# Base_SMD.net
KiCad netlist of a schematic drawn in EAGLE
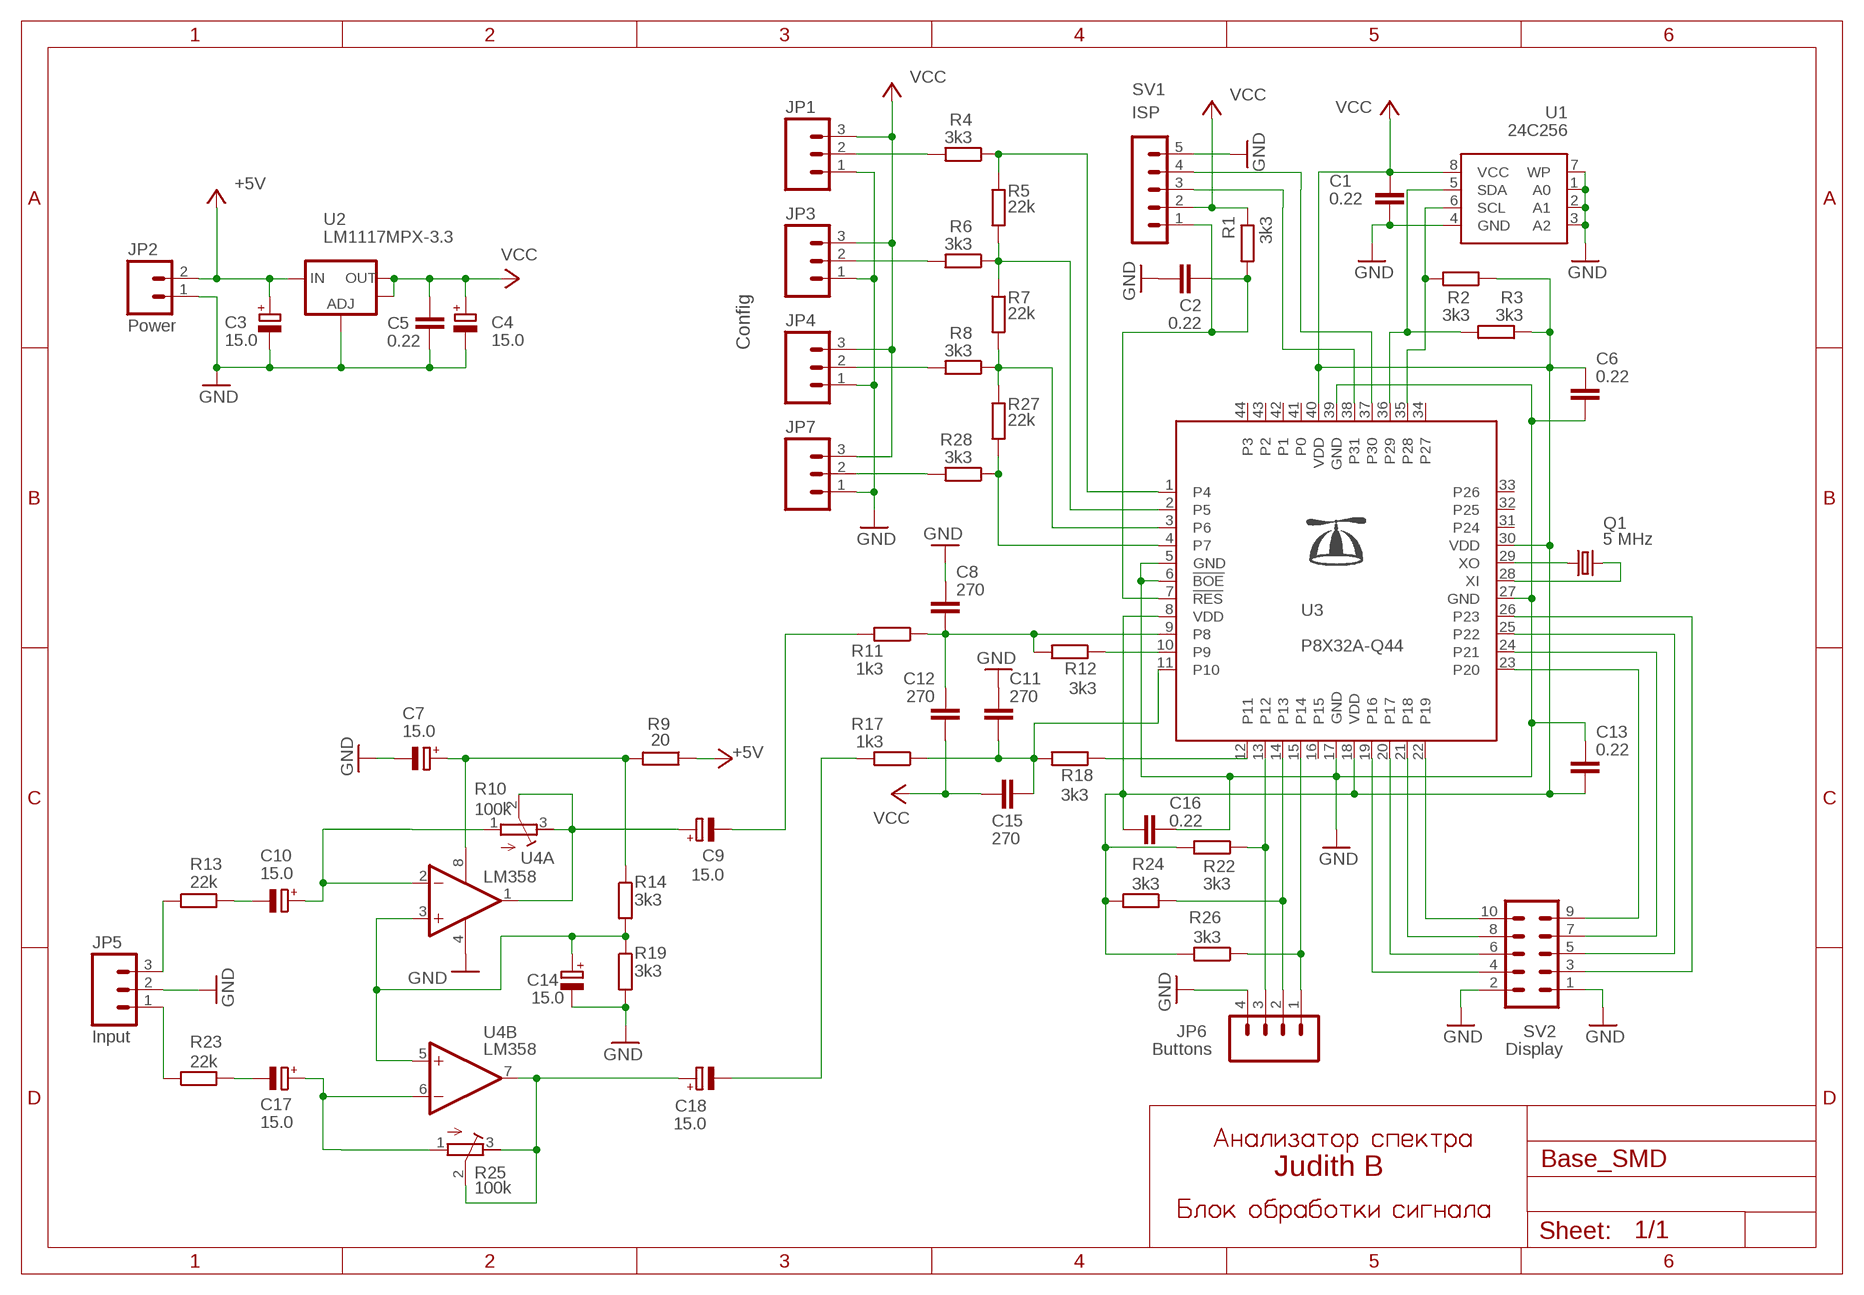
[diagram p0: schematic, sheet 1]

(export (version "E")
  (design (tool "Eeschema 10.0.6"))
  (components
    (comp (ref "C1")
      (value "0.22")
      (footprint "eagle-import:C0805")
      (libsource (lib "eagle-import") (part "C-EUC0805"))
    )
    (comp (ref "C2")
      (value "0.22")
      (footprint "eagle-import:C0805")
      (libsource (lib "eagle-import") (part "C-EUC0805"))
    )
    (comp (ref "C3")
      (value "15.0")
      (footprint "eagle-import:SMC_B")
      (libsource (lib "eagle-import") (part "CPOL-EUSMCB"))
    )
    (comp (ref "C4")
      (value "15.0")
      (footprint "eagle-import:SMC_B")
      (libsource (lib "eagle-import") (part "CPOL-EUSMCB"))
    )
    (comp (ref "C5")
      (value "0.22")
      (footprint "eagle-import:C0805")
      (libsource (lib "eagle-import") (part "C-EUC0805"))
    )
    (comp (ref "C6")
      (value "0.22")
      (footprint "eagle-import:C0805")
      (libsource (lib "eagle-import") (part "C-EUC0805"))
    )
    (comp (ref "C7")
      (value "15.0")
      (footprint "eagle-import:SMC_B")
      (libsource (lib "eagle-import") (part "CPOL-EUSMCB"))
    )
    (comp (ref "C8")
      (value "270")
      (footprint "eagle-import:C0805")
      (libsource (lib "eagle-import") (part "C-EUC0805"))
    )
    (comp (ref "C9")
      (value "15.0")
      (footprint "eagle-import:SMC_B")
      (libsource (lib "eagle-import") (part "CPOL-EUSMCB"))
    )
    (comp (ref "C10")
      (value "15.0")
      (footprint "eagle-import:SMC_B")
      (libsource (lib "eagle-import") (part "CPOL-EUSMCB"))
    )
    (comp (ref "C11")
      (value "270")
      (footprint "eagle-import:C0805")
      (libsource (lib "eagle-import") (part "C-EUC0805"))
    )
    (comp (ref "C12")
      (value "270")
      (footprint "eagle-import:C0805")
      (libsource (lib "eagle-import") (part "C-EUC0805"))
    )
    (comp (ref "C13")
      (value "0.22")
      (footprint "eagle-import:C0805")
      (libsource (lib "eagle-import") (part "C-EUC0805"))
    )
    (comp (ref "C14")
      (value "15.0")
      (footprint "eagle-import:SMC_B")
      (libsource (lib "eagle-import") (part "CPOL-EUSMCB"))
    )
    (comp (ref "C15")
      (value "270")
      (footprint "eagle-import:C0805")
      (libsource (lib "eagle-import") (part "C-EUC0805"))
    )
    (comp (ref "C16")
      (value "0.22")
      (footprint "eagle-import:C0805")
      (libsource (lib "eagle-import") (part "C-EUC0805"))
    )
    (comp (ref "C17")
      (value "15.0")
      (footprint "eagle-import:SMC_B")
      (libsource (lib "eagle-import") (part "CPOL-EUSMCB"))
    )
    (comp (ref "C18")
      (value "15.0")
      (footprint "eagle-import:SMC_B")
      (libsource (lib "eagle-import") (part "CPOL-EUSMCB"))
    )
    (comp (ref "JP1")
      (value "M03PTH")
      (footprint "eagle-import:1X03")
      (libsource (lib "eagle-import") (part "M03PTH"))
    )
    (comp (ref "JP2")
      (value "Power")
      (footprint "eagle-import:1X02")
      (libsource (lib "eagle-import") (part "M02PTH"))
    )
    (comp (ref "JP3")
      (value "M03PTH")
      (footprint "eagle-import:1X03")
      (libsource (lib "eagle-import") (part "M03PTH"))
    )
    (comp (ref "JP4")
      (value "M03PTH")
      (footprint "eagle-import:1X03")
      (libsource (lib "eagle-import") (part "M03PTH"))
    )
    (comp (ref "JP5")
      (value "Input")
      (footprint "eagle-import:1X03")
      (libsource (lib "eagle-import") (part "M03PTH"))
    )
    (comp (ref "JP6")
      (value "Buttons")
      (footprint "eagle-import:1X04")
      (libsource (lib "eagle-import") (part "M04PTH"))
    )
    (comp (ref "JP7")
      (value "M03PTH")
      (footprint "eagle-import:1X03")
      (libsource (lib "eagle-import") (part "M03PTH"))
    )
    (comp (ref "Q1")
      (value "5 MHz")
      (footprint "eagle-import:HC49_S")
      (libsource (lib "eagle-import") (part "CRYSTALHC49S"))
    )
    (comp (ref "R1")
      (value "3k3")
      (footprint "eagle-import:R0805")
      (libsource (lib "eagle-import") (part "R-0805"))
    )
    (comp (ref "R2")
      (value "3k3")
      (footprint "eagle-import:R0805")
      (libsource (lib "eagle-import") (part "R-0805"))
    )
    (comp (ref "R3")
      (value "3k3")
      (footprint "eagle-import:R0805")
      (libsource (lib "eagle-import") (part "R-0805"))
    )
    (comp (ref "R4")
      (value "3k3")
      (footprint "eagle-import:R0805")
      (libsource (lib "eagle-import") (part "R-0805"))
    )
    (comp (ref "R5")
      (value "22k")
      (footprint "eagle-import:R0805")
      (libsource (lib "eagle-import") (part "R-0805"))
    )
    (comp (ref "R6")
      (value "3k3")
      (footprint "eagle-import:R0805")
      (libsource (lib "eagle-import") (part "R-0805"))
    )
    (comp (ref "R7")
      (value "22k")
      (footprint "eagle-import:R0805")
      (libsource (lib "eagle-import") (part "R-0805"))
    )
    (comp (ref "R8")
      (value "3k3")
      (footprint "eagle-import:R0805")
      (libsource (lib "eagle-import") (part "R-0805"))
    )
    (comp (ref "R9")
      (value "20")
      (footprint "eagle-import:R0805")
      (libsource (lib "eagle-import") (part "R-0805"))
    )
    (comp (ref "R10")
      (value "100k")
      (footprint "eagle-import:RTRIM3296W")
      (libsource (lib "eagle-import") (part "R-TRIMM3296W"))
    )
    (comp (ref "R11")
      (value "1k3")
      (footprint "eagle-import:R0805")
      (libsource (lib "eagle-import") (part "R-0805"))
    )
    (comp (ref "R12")
      (value "3k3")
      (footprint "eagle-import:R0805")
      (libsource (lib "eagle-import") (part "R-0805"))
    )
    (comp (ref "R13")
      (value "22k")
      (footprint "eagle-import:R0805")
      (libsource (lib "eagle-import") (part "R-0805"))
    )
    (comp (ref "R14")
      (value "3k3")
      (footprint "eagle-import:R0805")
      (libsource (lib "eagle-import") (part "R-0805"))
    )
    (comp (ref "R17")
      (value "1k3")
      (footprint "eagle-import:R0805")
      (libsource (lib "eagle-import") (part "R-0805"))
    )
    (comp (ref "R18")
      (value "3k3")
      (footprint "eagle-import:R0805")
      (libsource (lib "eagle-import") (part "R-0805"))
    )
    (comp (ref "R19")
      (value "3k3")
      (footprint "eagle-import:R0805")
      (libsource (lib "eagle-import") (part "R-0805"))
    )
    (comp (ref "R22")
      (value "3k3")
      (footprint "eagle-import:R0805")
      (libsource (lib "eagle-import") (part "R-0805"))
    )
    (comp (ref "R23")
      (value "22k")
      (footprint "eagle-import:R0805")
      (libsource (lib "eagle-import") (part "R-0805"))
    )
    (comp (ref "R24")
      (value "3k3")
      (footprint "eagle-import:R0805")
      (libsource (lib "eagle-import") (part "R-0805"))
    )
    (comp (ref "R25")
      (value "100k")
      (footprint "eagle-import:RTRIM3296W")
      (libsource (lib "eagle-import") (part "R-TRIMM3296W"))
    )
    (comp (ref "R26")
      (value "3k3")
      (footprint "eagle-import:R0805")
      (libsource (lib "eagle-import") (part "R-0805"))
    )
    (comp (ref "R27")
      (value "22k")
      (footprint "eagle-import:R0805")
      (libsource (lib "eagle-import") (part "R-0805"))
    )
    (comp (ref "R28")
      (value "3k3")
      (footprint "eagle-import:R0805")
      (libsource (lib "eagle-import") (part "R-0805"))
    )
    (comp (ref "SV1")
      (value "ISP")
      (footprint "eagle-import:MA05-1")
      (libsource (lib "eagle-import") (part "MA05-1"))
    )
    (comp (ref "SV2")
      (value "Display")
      (footprint "eagle-import:MA05-2")
      (libsource (lib "eagle-import") (part "MA05-2"))
    )
    (comp (ref "U1")
      (value "24C256")
      (footprint "eagle-import:SO08")
      (libsource (lib "eagle-import") (part "I2C_EEPROM"))
    )
    (comp (ref "U2")
      (value "LM1117MPX-3.3")
      (footprint "eagle-import:SOT223")
      (libsource (lib "eagle-import") (part "V_REG_LM1117SOT223"))
    )
    (comp (ref "U3")
      (value "P8X32A-Q44")
      (footprint "eagle-import:SQFP-S-10X10-44")
      (libsource (lib "eagle-import") (part "P8X32A-Q44"))
    )
    (comp (ref "U4")
      (value "LM358")
      (footprint "eagle-import:SO08")
      (libsource (lib "eagle-import") (part "TL072D"))
    )
  )
  (nets
    (net (code "1") (name "+5V") (class "Default")
      (node (ref "C3") (pin "+") (pinfunction "+_+") (pintype "passive"))
      (node (ref "JP2") (pin "2") (pinfunction "2_2") (pintype "passive"))
      (node (ref "R9") (pin "1") (pinfunction "1_1") (pintype "passive"))
      (node (ref "U2") (pin "3") (pinfunction "IN_3") (pintype "input"))
    )
    (net (code "2") (name "GND") (class "Default")
      (node (ref "C1") (pin "2") (pinfunction "2_2") (pintype "passive"))
      (node (ref "C11") (pin "1") (pinfunction "1_1") (pintype "passive"))
      (node (ref "C13") (pin "1") (pinfunction "1_1") (pintype "passive"))
      (node (ref "C14") (pin "-") (pinfunction "-_-") (pintype "passive"))
      (node (ref "C16") (pin "2") (pinfunction "2_2") (pintype "passive"))
      (node (ref "C2") (pin "1") (pinfunction "1_1") (pintype "passive"))
      (node (ref "C3") (pin "-") (pinfunction "-_-") (pintype "passive"))
      (node (ref "C4") (pin "-") (pinfunction "-_-") (pintype "passive"))
      (node (ref "C5") (pin "1") (pinfunction "1_1") (pintype "passive"))
      (node (ref "C6") (pin "2") (pinfunction "2_2") (pintype "passive"))
      (node (ref "C7") (pin "-") (pinfunction "-_-") (pintype "passive"))
      (node (ref "C8") (pin "1") (pinfunction "1_1") (pintype "passive"))
      (node (ref "JP1") (pin "1") (pinfunction "1_1") (pintype "passive"))
      (node (ref "JP2") (pin "1") (pinfunction "1_1") (pintype "passive"))
      (node (ref "JP3") (pin "1") (pinfunction "1_1") (pintype "passive"))
      (node (ref "JP4") (pin "1") (pinfunction "1_1") (pintype "passive"))
      (node (ref "JP5") (pin "2") (pinfunction "2_2") (pintype "passive"))
      (node (ref "JP6") (pin "4") (pinfunction "4_4") (pintype "passive"))
      (node (ref "JP7") (pin "1") (pinfunction "1_1") (pintype "passive"))
      (node (ref "R19") (pin "2") (pinfunction "2_2") (pintype "passive"))
      (node (ref "SV1") (pin "5") (pinfunction "5_5") (pintype "passive"))
      (node (ref "SV2") (pin "1") (pinfunction "1_1") (pintype "passive"))
      (node (ref "SV2") (pin "2") (pinfunction "2_2") (pintype "passive"))
      (node (ref "U1") (pin "1") (pinfunction "A0_1") (pintype "bidirectional"))
      (node (ref "U1") (pin "2") (pinfunction "A1_2") (pintype "bidirectional"))
      (node (ref "U1") (pin "3") (pinfunction "A2_3") (pintype "bidirectional"))
      (node (ref "U1") (pin "4") (pinfunction "GND_4") (pintype "bidirectional"))
      (node (ref "U1") (pin "7") (pinfunction "WP_7") (pintype "bidirectional"))
      (node (ref "U2") (pin "1") (pinfunction "ADJ_1") (pintype "input"))
      (node (ref "U3") (pin "17") (pinfunction "GND_17") (pintype "bidirectional"))
      (node (ref "U3") (pin "27") (pinfunction "GND_27") (pintype "bidirectional"))
      (node (ref "U3") (pin "39") (pinfunction "GND_39") (pintype "bidirectional"))
      (node (ref "U3") (pin "5") (pinfunction "GND_5") (pintype "bidirectional"))
      (node (ref "U3") (pin "6") (pinfunction "~{BOE}_6") (pintype "input"))
      (node (ref "U4") (pin "4") (pinfunction "V-_4") (pintype "power_in"))
    )
    (net (code "3") (name "Net-(C9-Pad-)") (class "Default")
      (node (ref "C9") (pin "-") (pinfunction "-_-") (pintype "passive"))
      (node (ref "R11") (pin "2") (pinfunction "2_2") (pintype "passive"))
    )
    (net (code "4") (name "Net-(C10-Pad-)") (class "Default")
      (node (ref "C10") (pin "-") (pinfunction "-_-") (pintype "passive"))
      (node (ref "R13") (pin "2") (pinfunction "2_2") (pintype "passive"))
    )
    (net (code "5") (name "Net-(C17-Pad-)") (class "Default")
      (node (ref "C17") (pin "-") (pinfunction "-_-") (pintype "passive"))
      (node (ref "R23") (pin "2") (pinfunction "2_2") (pintype "passive"))
    )
    (net (code "6") (name "Net-(C18-Pad-)") (class "Default")
      (node (ref "C18") (pin "-") (pinfunction "-_-") (pintype "passive"))
      (node (ref "R17") (pin "2") (pinfunction "2_2") (pintype "passive"))
    )
    (net (code "7") (name "Net-(JP1-Pad2)") (class "Default")
      (node (ref "JP1") (pin "2") (pinfunction "2_2") (pintype "passive"))
      (node (ref "R4") (pin "2") (pinfunction "2_2") (pintype "passive"))
    )
    (net (code "8") (name "Net-(JP3-Pad2)") (class "Default")
      (node (ref "JP3") (pin "2") (pinfunction "2_2") (pintype "passive"))
      (node (ref "R6") (pin "2") (pinfunction "2_2") (pintype "passive"))
    )
    (net (code "9") (name "Net-(JP4-Pad2)") (class "Default")
      (node (ref "JP4") (pin "2") (pinfunction "2_2") (pintype "passive"))
      (node (ref "R8") (pin "2") (pinfunction "2_2") (pintype "passive"))
    )
    (net (code "10") (name "Net-(JP5-Pad1)") (class "Default")
      (node (ref "JP5") (pin "1") (pinfunction "1_1") (pintype "passive"))
      (node (ref "R23") (pin "1") (pinfunction "1_1") (pintype "passive"))
    )
    (net (code "11") (name "Net-(JP5-Pad3)") (class "Default")
      (node (ref "JP5") (pin "3") (pinfunction "3_3") (pintype "passive"))
      (node (ref "R13") (pin "1") (pinfunction "1_1") (pintype "passive"))
    )
    (net (code "12") (name "Net-(JP7-Pad2)") (class "Default")
      (node (ref "JP7") (pin "2") (pinfunction "2_2") (pintype "passive"))
      (node (ref "R28") (pin "2") (pinfunction "2_2") (pintype "passive"))
    )
    (net (code "13") (name "Net-(R10-A)") (class "Default")
      (node (ref "C9") (pin "+") (pinfunction "+_+") (pintype "passive"))
      (node (ref "R10") (pin "2") (pinfunction "S_2") (pintype "passive"))
      (node (ref "R10") (pin "3") (pinfunction "A_3") (pintype "passive"))
      (node (ref "U4") (pin "1") (pinfunction "OUT_1") (pintype "output"))
    )
    (net (code "14") (name "Net-(R10-E)") (class "Default")
      (node (ref "C10") (pin "+") (pinfunction "+_+") (pintype "passive"))
      (node (ref "R10") (pin "1") (pinfunction "E_1") (pintype "passive"))
      (node (ref "U4") (pin "2") (pinfunction "-IN_2") (pintype "input"))
    )
    (net (code "15") (name "Net-(R25-A)") (class "Default")
      (node (ref "C18") (pin "+") (pinfunction "+_+") (pintype "passive"))
      (node (ref "R25") (pin "2") (pinfunction "S_2") (pintype "passive"))
      (node (ref "R25") (pin "3") (pinfunction "A_3") (pintype "passive"))
      (node (ref "U4") (pin "7") (pinfunction "OUT_7") (pintype "output"))
    )
    (net (code "16") (name "Net-(R25-E)") (class "Default")
      (node (ref "C17") (pin "+") (pinfunction "+_+") (pintype "passive"))
      (node (ref "R25") (pin "1") (pinfunction "E_1") (pintype "passive"))
      (node (ref "U4") (pin "6") (pinfunction "-IN_6") (pintype "input"))
    )
    (net (code "17") (name "Net-(U1-SCL)") (class "Default")
      (node (ref "R2") (pin "2") (pinfunction "2_2") (pintype "passive"))
      (node (ref "U1") (pin "6") (pinfunction "SCL_6") (pintype "bidirectional"))
      (node (ref "U3") (pin "35") (pinfunction "P28_35") (pintype "bidirectional"))
    )
    (net (code "18") (name "Net-(U1-SDA)") (class "Default")
      (node (ref "R3") (pin "2") (pinfunction "2_2") (pintype "passive"))
      (node (ref "U1") (pin "5") (pinfunction "SDA_5") (pintype "bidirectional"))
      (node (ref "U3") (pin "36") (pinfunction "P29_36") (pintype "bidirectional"))
    )
    (net (code "19") (name "Net-(U3-P4)") (class "Default")
      (node (ref "R4") (pin "1") (pinfunction "1_1") (pintype "passive"))
      (node (ref "R5") (pin "1") (pinfunction "1_1") (pintype "passive"))
      (node (ref "U3") (pin "1") (pinfunction "P4_1") (pintype "bidirectional"))
    )
    (net (code "20") (name "Net-(U3-P5)") (class "Default")
      (node (ref "R5") (pin "2") (pinfunction "2_2") (pintype "passive"))
      (node (ref "R6") (pin "1") (pinfunction "1_1") (pintype "passive"))
      (node (ref "R7") (pin "1") (pinfunction "1_1") (pintype "passive"))
      (node (ref "U3") (pin "2") (pinfunction "P5_2") (pintype "bidirectional"))
    )
    (net (code "21") (name "Net-(U3-P6)") (class "Default")
      (node (ref "R27") (pin "1") (pinfunction "1_1") (pintype "passive"))
      (node (ref "R7") (pin "2") (pinfunction "2_2") (pintype "passive"))
      (node (ref "R8") (pin "1") (pinfunction "1_1") (pintype "passive"))
      (node (ref "U3") (pin "3") (pinfunction "P6_3") (pintype "bidirectional"))
    )
    (net (code "22") (name "Net-(U3-P7)") (class "Default")
      (node (ref "R27") (pin "2") (pinfunction "2_2") (pintype "passive"))
      (node (ref "R28") (pin "1") (pinfunction "1_1") (pintype "passive"))
      (node (ref "U3") (pin "4") (pinfunction "P7_4") (pintype "bidirectional"))
    )
    (net (code "23") (name "Net-(U3-P8)") (class "Default")
      (node (ref "C12") (pin "2") (pinfunction "2_2") (pintype "passive"))
      (node (ref "C8") (pin "2") (pinfunction "2_2") (pintype "passive"))
      (node (ref "R11") (pin "1") (pinfunction "1_1") (pintype "passive"))
      (node (ref "R12") (pin "2") (pinfunction "2_2") (pintype "passive"))
      (node (ref "U3") (pin "9") (pinfunction "P8_9") (pintype "bidirectional"))
    )
    (net (code "24") (name "Net-(U3-P9)") (class "Default")
      (node (ref "R12") (pin "1") (pinfunction "1_1") (pintype "passive"))
      (node (ref "U3") (pin "10") (pinfunction "P9_10") (pintype "bidirectional"))
    )
    (net (code "25") (name "Net-(U3-P10)") (class "Default")
      (node (ref "C11") (pin "2") (pinfunction "2_2") (pintype "passive"))
      (node (ref "C15") (pin "2") (pinfunction "2_2") (pintype "passive"))
      (node (ref "R17") (pin "1") (pinfunction "1_1") (pintype "passive"))
      (node (ref "R18") (pin "2") (pinfunction "2_2") (pintype "passive"))
      (node (ref "U3") (pin "11") (pinfunction "P10_11") (pintype "bidirectional"))
    )
    (net (code "26") (name "Net-(U3-P11)") (class "Default")
      (node (ref "R18") (pin "1") (pinfunction "1_1") (pintype "passive"))
      (node (ref "U3") (pin "12") (pinfunction "P11_12") (pintype "bidirectional"))
    )
    (net (code "27") (name "Net-(U3-P12)") (class "Default")
      (node (ref "JP6") (pin "3") (pinfunction "3_3") (pintype "passive"))
      (node (ref "R22") (pin "1") (pinfunction "1_1") (pintype "passive"))
      (node (ref "U3") (pin "13") (pinfunction "P12_13") (pintype "bidirectional"))
    )
    (net (code "28") (name "Net-(U3-P13)") (class "Default")
      (node (ref "JP6") (pin "2") (pinfunction "2_2") (pintype "passive"))
      (node (ref "R24") (pin "1") (pinfunction "1_1") (pintype "passive"))
      (node (ref "U3") (pin "14") (pinfunction "P13_14") (pintype "bidirectional"))
    )
    (net (code "29") (name "Net-(U3-P14)") (class "Default")
      (node (ref "JP6") (pin "1") (pinfunction "1_1") (pintype "passive"))
      (node (ref "R26") (pin "1") (pinfunction "1_1") (pintype "passive"))
      (node (ref "U3") (pin "15") (pinfunction "P14_15") (pintype "bidirectional"))
    )
    (net (code "30") (name "Net-(U3-P16)") (class "Default")
      (node (ref "SV2") (pin "4") (pinfunction "4_4") (pintype "passive"))
      (node (ref "U3") (pin "19") (pinfunction "P16_19") (pintype "bidirectional"))
    )
    (net (code "31") (name "Net-(U3-P17)") (class "Default")
      (node (ref "SV2") (pin "6") (pinfunction "6_6") (pintype "passive"))
      (node (ref "U3") (pin "20") (pinfunction "P17_20") (pintype "bidirectional"))
    )
    (net (code "32") (name "Net-(U3-P18)") (class "Default")
      (node (ref "SV2") (pin "8") (pinfunction "8_8") (pintype "passive"))
      (node (ref "U3") (pin "21") (pinfunction "P18_21") (pintype "bidirectional"))
    )
    (net (code "33") (name "Net-(U3-P19)") (class "Default")
      (node (ref "SV2") (pin "10") (pinfunction "10_10") (pintype "passive"))
      (node (ref "U3") (pin "22") (pinfunction "P19_22") (pintype "bidirectional"))
    )
    (net (code "34") (name "Net-(U3-P20)") (class "Default")
      (node (ref "SV2") (pin "9") (pinfunction "9_9") (pintype "passive"))
      (node (ref "U3") (pin "23") (pinfunction "P20_23") (pintype "bidirectional"))
    )
    (net (code "35") (name "Net-(U3-P21)") (class "Default")
      (node (ref "SV2") (pin "7") (pinfunction "7_7") (pintype "passive"))
      (node (ref "U3") (pin "24") (pinfunction "P21_24") (pintype "bidirectional"))
    )
    (net (code "36") (name "Net-(U3-P22)") (class "Default")
      (node (ref "SV2") (pin "5") (pinfunction "5_5") (pintype "passive"))
      (node (ref "U3") (pin "25") (pinfunction "P22_25") (pintype "bidirectional"))
    )
    (net (code "37") (name "Net-(U3-P23)") (class "Default")
      (node (ref "SV2") (pin "3") (pinfunction "3_3") (pintype "passive"))
      (node (ref "U3") (pin "26") (pinfunction "P23_26") (pintype "bidirectional"))
    )
    (net (code "38") (name "Net-(U3-P30)") (class "Default")
      (node (ref "SV1") (pin "4") (pinfunction "4_4") (pintype "passive"))
      (node (ref "U3") (pin "37") (pinfunction "P30_37") (pintype "bidirectional"))
    )
    (net (code "39") (name "Net-(U3-P31)") (class "Default")
      (node (ref "SV1") (pin "3") (pinfunction "3_3") (pintype "passive"))
      (node (ref "U3") (pin "38") (pinfunction "P31_38") (pintype "bidirectional"))
    )
    (net (code "40") (name "Net-(U3-XI)") (class "Default")
      (node (ref "Q1") (pin "2") (pinfunction "2_2") (pintype "passive"))
      (node (ref "U3") (pin "28") (pinfunction "XI_28") (pintype "input"))
    )
    (net (code "41") (name "Net-(U3-XO)") (class "Default")
      (node (ref "Q1") (pin "1") (pinfunction "1_1") (pintype "passive"))
      (node (ref "U3") (pin "29") (pinfunction "XO_29") (pintype "output"))
    )
    (net (code "42") (name "Net-(U3-~{RES})") (class "Default")
      (node (ref "C2") (pin "2") (pinfunction "2_2") (pintype "passive"))
      (node (ref "R1") (pin "2") (pinfunction "2_2") (pintype "passive"))
      (node (ref "SV1") (pin "1") (pinfunction "1_1") (pintype "passive"))
      (node (ref "U3") (pin "7") (pinfunction "~{RES}_7") (pintype "bidirectional"))
    )
    (net (code "43") (name "Net-(U4A-+IN)") (class "Default")
      (node (ref "C14") (pin "+") (pinfunction "+_+") (pintype "passive"))
      (node (ref "R14") (pin "2") (pinfunction "2_2") (pintype "passive"))
      (node (ref "R19") (pin "1") (pinfunction "1_1") (pintype "passive"))
      (node (ref "U4") (pin "3") (pinfunction "+IN_3") (pintype "input"))
      (node (ref "U4") (pin "5") (pinfunction "+IN_5") (pintype "input"))
    )
    (net (code "44") (name "Net-(U4C-V+)") (class "Default")
      (node (ref "C7") (pin "+") (pinfunction "+_+") (pintype "passive"))
      (node (ref "R14") (pin "1") (pinfunction "1_1") (pintype "passive"))
      (node (ref "R9") (pin "2") (pinfunction "2_2") (pintype "passive"))
      (node (ref "U4") (pin "8") (pinfunction "V+_8") (pintype "power_in"))
    )
    (net (code "45") (name "VCC") (class "Default")
      (node (ref "C1") (pin "1") (pinfunction "1_1") (pintype "passive"))
      (node (ref "C12") (pin "1") (pinfunction "1_1") (pintype "passive"))
      (node (ref "C13") (pin "2") (pinfunction "2_2") (pintype "passive"))
      (node (ref "C15") (pin "1") (pinfunction "1_1") (pintype "passive"))
      (node (ref "C16") (pin "1") (pinfunction "1_1") (pintype "passive"))
      (node (ref "C4") (pin "+") (pinfunction "+_+") (pintype "passive"))
      (node (ref "C5") (pin "2") (pinfunction "2_2") (pintype "passive"))
      (node (ref "C6") (pin "1") (pinfunction "1_1") (pintype "passive"))
      (node (ref "JP1") (pin "3") (pinfunction "3_3") (pintype "passive"))
      (node (ref "JP3") (pin "3") (pinfunction "3_3") (pintype "passive"))
      (node (ref "JP4") (pin "3") (pinfunction "3_3") (pintype "passive"))
      (node (ref "JP7") (pin "3") (pinfunction "3_3") (pintype "passive"))
      (node (ref "R1") (pin "1") (pinfunction "1_1") (pintype "passive"))
      (node (ref "R2") (pin "1") (pinfunction "1_1") (pintype "passive"))
      (node (ref "R22") (pin "2") (pinfunction "2_2") (pintype "passive"))
      (node (ref "R24") (pin "2") (pinfunction "2_2") (pintype "passive"))
      (node (ref "R26") (pin "2") (pinfunction "2_2") (pintype "passive"))
      (node (ref "R3") (pin "1") (pinfunction "1_1") (pintype "passive"))
      (node (ref "SV1") (pin "2") (pinfunction "2_2") (pintype "passive"))
      (node (ref "U1") (pin "8") (pinfunction "VCC_8") (pintype "bidirectional"))
      (node (ref "U2") (pin "2") (pinfunction "OUT_2") (pintype "output"))
      (node (ref "U2") (pin "4") (pinfunction "OUT_4") (pintype "output"))
      (node (ref "U3") (pin "18") (pinfunction "VDD_18") (pintype "bidirectional"))
      (node (ref "U3") (pin "30") (pinfunction "VDD_30") (pintype "bidirectional"))
      (node (ref "U3") (pin "40") (pinfunction "VDD_40") (pintype "bidirectional"))
      (node (ref "U3") (pin "8") (pinfunction "VDD_8") (pintype "bidirectional"))
    )
    (net (code "46") (name "unconnected-(U3-P0-Pad41)") (class "Default")
      (node (ref "U3") (pin "41") (pinfunction "P0_41") (pintype "bidirectional"))
    )
    (net (code "47") (name "unconnected-(U3-P1-Pad42)") (class "Default")
      (node (ref "U3") (pin "42") (pinfunction "P1_42") (pintype "bidirectional"))
    )
    (net (code "48") (name "unconnected-(U3-P2-Pad43)") (class "Default")
      (node (ref "U3") (pin "43") (pinfunction "P2_43") (pintype "bidirectional"))
    )
    (net (code "49") (name "unconnected-(U3-P3-Pad44)") (class "Default")
      (node (ref "U3") (pin "44") (pinfunction "P3_44") (pintype "bidirectional"))
    )
    (net (code "50") (name "unconnected-(U3-P15-Pad16)") (class "Default")
      (node (ref "U3") (pin "16") (pinfunction "P15_16") (pintype "bidirectional"))
    )
    (net (code "51") (name "unconnected-(U3-P24-Pad31)") (class "Default")
      (node (ref "U3") (pin "31") (pinfunction "P24_31") (pintype "bidirectional"))
    )
    (net (code "52") (name "unconnected-(U3-P25-Pad32)") (class "Default")
      (node (ref "U3") (pin "32") (pinfunction "P25_32") (pintype "bidirectional"))
    )
    (net (code "53") (name "unconnected-(U3-P26-Pad33)") (class "Default")
      (node (ref "U3") (pin "33") (pinfunction "P26_33") (pintype "bidirectional"))
    )
    (net (code "54") (name "unconnected-(U3-P27-Pad34)") (class "Default")
      (node (ref "U3") (pin "34") (pinfunction "P27_34") (pintype "bidirectional"))
    )
  )
)
